# ModulCzujnika.net
KiCad netlist of a schematic drawn in EAGLE
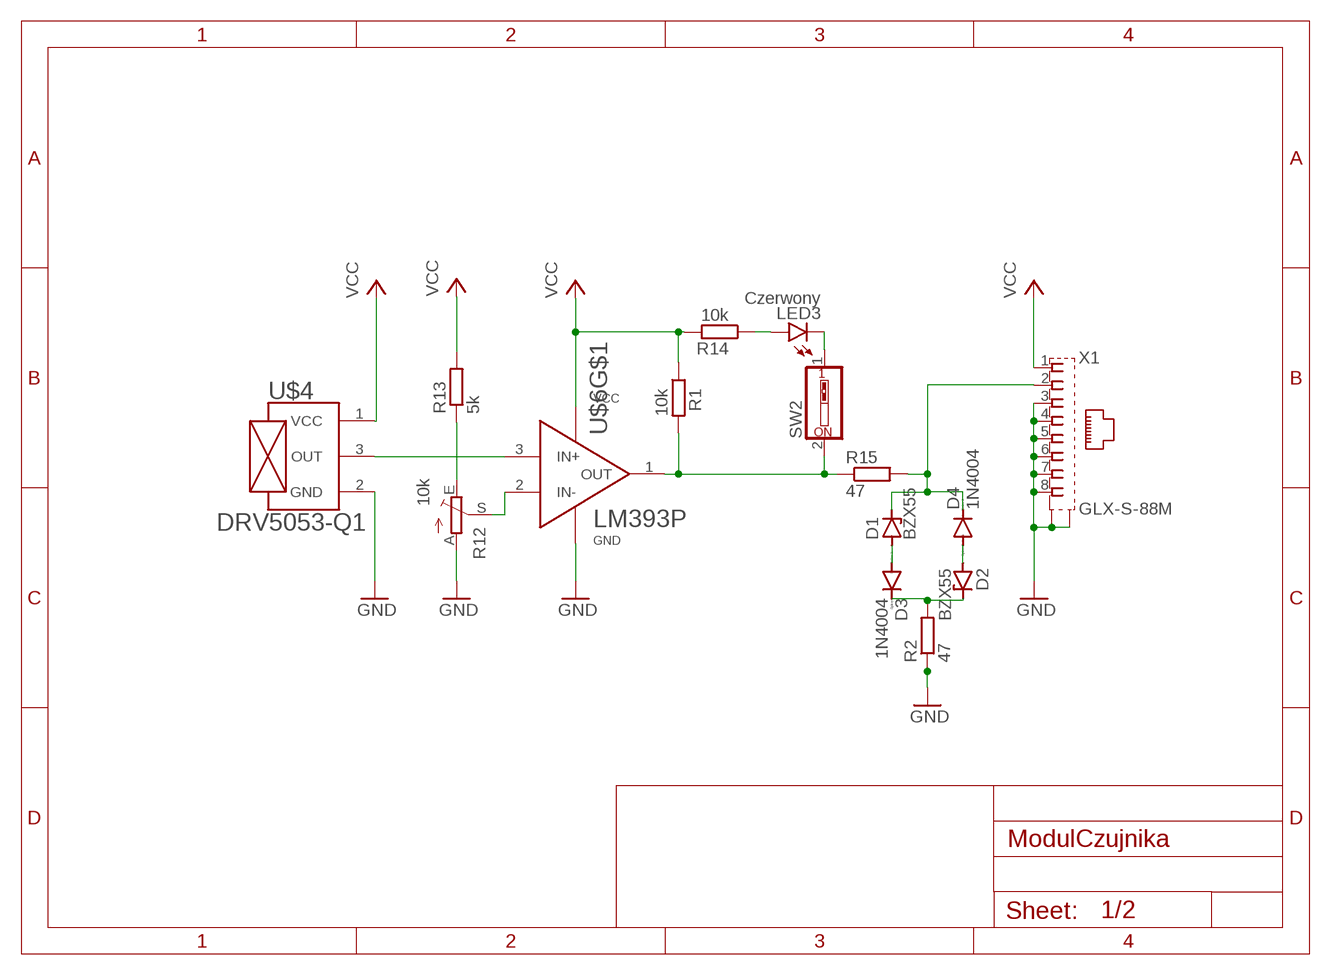
[diagram p0: schematic, sheet 1]

(export (version "E")
  (design (tool "Eeschema 10.0.6"))
  (components
    (comp (ref "D1")
      (value "BZX55")
      (footprint "eagle-import:DO35Z10")
      (libsource (lib "eagle-import") (part "BZX55"))
    )
    (comp (ref "D2")
      (value "BZX55")
      (footprint "eagle-import:DO35Z10")
      (libsource (lib "eagle-import") (part "BZX55"))
    )
    (comp (ref "D3")
      (value "1N4004")
      (footprint "eagle-import:DO41-10")
      (libsource (lib "eagle-import") (part "1N4004"))
    )
    (comp (ref "D4")
      (value "1N4004")
      (footprint "eagle-import:DO41-10")
      (libsource (lib "eagle-import") (part "1N4004"))
    )
    (comp (ref "LED3")
      (value "Czerwony")
      (footprint "eagle-import:LED5MM")
      (libsource (lib "eagle-import") (part "LED5MM"))
    )
    (comp (ref "R1")
      (value "10k")
      (footprint "eagle-import:0207_7")
      (libsource (lib "eagle-import") (part "R-EU_0207/7"))
    )
    (comp (ref "R2")
      (value "47")
      (footprint "eagle-import:0207_7")
      (libsource (lib "eagle-import") (part "R-EU_0207/7"))
    )
    (comp (ref "R12")
      (value "10k")
      (footprint "eagle-import:CA6V")
      (libsource (lib "eagle-import") (part "TRIM_EU-CA6V"))
    )
    (comp (ref "R13")
      (value "5k")
      (footprint "eagle-import:0207_7")
      (libsource (lib "eagle-import") (part "R-EU_0207/7"))
    )
    (comp (ref "R14")
      (value "10k")
      (footprint "eagle-import:0207_7")
      (libsource (lib "eagle-import") (part "R-EU_0207/7"))
    )
    (comp (ref "R15")
      (value "47")
      (footprint "eagle-import:0207_7")
      (libsource (lib "eagle-import") (part "R-EU_0207/7"))
    )
    (comp (ref "SW2")
      (value "SW_DIP-1")
      (footprint "eagle-import:EDG-01")
      (libsource (lib "eagle-import") (part "SW_DIP-1"))
    )
    (comp (ref "U$4")
      (value "DRV5053-Q1")
      (footprint "eagle-import:TO-92")
      (libsource (lib "eagle-import") (part "DRV5053-Q1"))
    )
    (comp (ref "U$6")
      (value "LM393P")
      (footprint "eagle-import:R-PDIP-T8")
      (libsource (lib "eagle-import") (part "LM393P"))
    )
    (comp (ref "X1")
      (value "GLX-S-88M")
      (footprint "eagle-import:GLX-S-88M")
      (libsource (lib "eagle-import") (part "GLX-S-88M"))
    )
  )
  (nets
    (net (code "1") (name "GND") (class "Default")
      (node (ref "R12") (pin "A") (pinfunction "A_A") (pintype "passive"))
      (node (ref "R2") (pin "1") (pinfunction "1_1") (pintype "passive"))
      (node (ref "U$4") (pin "2") (pinfunction "GND_2") (pintype "power_in"))
      (node (ref "U$6") (pin "4") (pinfunction "GND_4") (pintype "bidirectional"))
      (node (ref "X1") (pin "3") (pinfunction "3_3") (pintype "passive"))
      (node (ref "X1") (pin "4") (pinfunction "4_4") (pintype "passive"))
      (node (ref "X1") (pin "5") (pinfunction "5_5") (pintype "passive"))
      (node (ref "X1") (pin "6") (pinfunction "6_6") (pintype "passive"))
      (node (ref "X1") (pin "7") (pinfunction "7_7") (pintype "passive"))
      (node (ref "X1") (pin "8") (pinfunction "8_8") (pintype "passive"))
      (node (ref "X1") (pin "S1") (pinfunction "S1_S1") (pintype "passive"))
      (node (ref "X1") (pin "S2") (pinfunction "S2_S2") (pintype "passive"))
    )
    (net (code "2") (name "Net-(D1-PadA)") (class "Default")
      (node (ref "D1") (pin "A") (pinfunction "A_A") (pintype "passive"))
      (node (ref "D3") (pin "A") (pinfunction "A_A") (pintype "passive"))
    )
    (net (code "3") (name "Net-(D1-PadC)") (class "Default")
      (node (ref "D1") (pin "C") (pinfunction "C_C") (pintype "passive"))
      (node (ref "D4") (pin "C") (pinfunction "C_C") (pintype "passive"))
      (node (ref "R15") (pin "2") (pinfunction "2_2") (pintype "passive"))
      (node (ref "X1") (pin "2") (pinfunction "2_2") (pintype "passive"))
    )
    (net (code "4") (name "Net-(D2-PadA)") (class "Default")
      (node (ref "D2") (pin "A") (pinfunction "A_A") (pintype "passive"))
      (node (ref "D4") (pin "A") (pinfunction "A_A") (pintype "passive"))
    )
    (net (code "5") (name "Net-(D2-PadC)") (class "Default")
      (node (ref "D2") (pin "C") (pinfunction "C_C") (pintype "passive"))
      (node (ref "D3") (pin "C") (pinfunction "C_C") (pintype "passive"))
      (node (ref "R2") (pin "2") (pinfunction "2_2") (pintype "passive"))
    )
    (net (code "6") (name "Net-(LED3-C)") (class "Default")
      (node (ref "LED3") (pin "K") (pinfunction "C_K") (pintype "passive"))
      (node (ref "SW2") (pin "1") (pinfunction "1_1") (pintype "passive"))
    )
    (net (code "7") (name "Net-(LED3-PadA)") (class "Default")
      (node (ref "LED3") (pin "A") (pinfunction "A_A") (pintype "passive"))
      (node (ref "R14") (pin "1") (pinfunction "1_1") (pintype "passive"))
    )
    (net (code "8") (name "Net-(R12-PadE)") (class "Default")
      (node (ref "R12") (pin "E") (pinfunction "E_E") (pintype "passive"))
      (node (ref "R13") (pin "1") (pinfunction "1_1") (pintype "passive"))
    )
    (net (code "9") (name "Net-(U$4-OUT)") (class "Default")
      (node (ref "U$4") (pin "3") (pinfunction "OUT_3") (pintype "bidirectional"))
      (node (ref "U$6") (pin "3") (pinfunction "IN+_3") (pintype "input"))
    )
    (net (code "10") (name "Net-(U$6A-IN-)") (class "Default")
      (node (ref "R12") (pin "S") (pinfunction "S_S") (pintype "passive"))
      (node (ref "U$6") (pin "2") (pinfunction "IN-_2") (pintype "input"))
    )
    (net (code "11") (name "Net-(U$6A-OUT)") (class "Default")
      (node (ref "R1") (pin "2") (pinfunction "2_2") (pintype "passive"))
      (node (ref "R15") (pin "1") (pinfunction "1_1") (pintype "passive"))
      (node (ref "SW2") (pin "2") (pinfunction "2_2") (pintype "passive"))
      (node (ref "U$6") (pin "1") (pinfunction "OUT_1") (pintype "bidirectional"))
    )
    (net (code "12") (name "VCC") (class "Default")
      (node (ref "R1") (pin "1") (pinfunction "1_1") (pintype "passive"))
      (node (ref "R13") (pin "2") (pinfunction "2_2") (pintype "passive"))
      (node (ref "R14") (pin "2") (pinfunction "2_2") (pintype "passive"))
      (node (ref "U$4") (pin "1") (pinfunction "VCC_1") (pintype "power_in"))
      (node (ref "U$6") (pin "8") (pinfunction "VCC_8") (pintype "bidirectional"))
      (node (ref "X1") (pin "1") (pinfunction "1_1") (pintype "passive"))
    )
  )
)
